# Nahid_s.net
KiCad netlist of a schematic drawn in Altium Designer
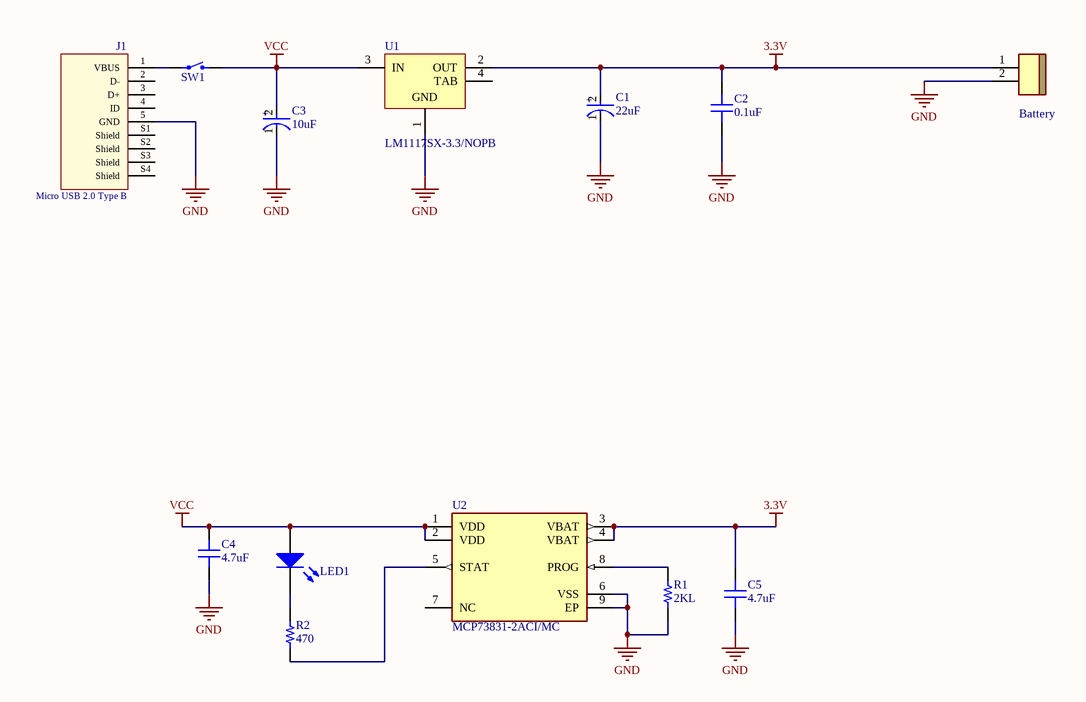
[diagram p0: Nahid's.SchDoc]

(export (version "E")
  (design (tool "Eeschema 10.0.6"))
  (components
    (comp (ref "Battery")
      (value "Battery")
      (footprint "JST B2B-PH-K")
      (description "Connector Header Through Hole 0.079\" (2.00mm)")
      (fields (field (name "PARTNUMBER") "B2B-PH-K-S(LF)(SN)"))
      (libsource (lib "Conn Terminal") (part "JST BxB-PH-K 2Pin"))
    )
    (comp (ref "C1")
      (value "22uF")
      (footprint "FP-EEH-G-MFG")
      (description "Conductive Polymer Hybrid Aluminum Electrolytic Capacitors 470uF ±20% 25V RADIAL SMT 10x10.2mm")
      (fields (field (name "TOLERANCE") "20%"))
      (libsource (lib "Altium Content Vault") (part "a00bbbee19879c290e62620ae7e47b1"))
    )
    (comp (ref "C2")
      (value "0.1uF")
      (footprint "CAP 0603_1608")
      (description "SMT Capacitor")
      (libsource (lib "Capacitor") (part "Cap 0603"))
    )
    (comp (ref "C3")
      (value "10uF")
      (footprint "FP-EEH-G-MFG")
      (description "Conductive Polymer Hybrid Aluminum Electrolytic Capacitors 470uF ±20% 25V RADIAL SMT 10x10.2mm")
      (fields (field (name "TOLERANCE") "20%"))
      (libsource (lib "Altium Content Vault") (part "a00bbbee19879c290e62620ae7e47b1"))
    )
    (comp (ref "C4")
      (value "4.7uF")
      (footprint "CAP 0603_1608")
      (description "SMT Capacitor")
      (libsource (lib "Capacitor") (part "Cap 0603"))
    )
    (comp (ref "C5")
      (value "4.7uF")
      (footprint "CAP 0603_1608")
      (description "SMT Capacitor")
      (libsource (lib "Capacitor") (part "Cap 0603"))
    )
    (comp (ref "J1")
      (value "Micro USB 2.0 Type B")
      (footprint "629105150521")
      (description "Micro USB 2.0 Type B Horizontal SMT 5 Contacts High Current WR-COM")
      (fields (field (name "PARTNUMBER") "629105150521") (field (name "PUBLISHER") "Wurth Elektronik"))
      (libsource (lib "Conn Usb") (part "Micro USB 2.0 Type B Horizontal (SMD) 629105150521"))
    )
    (comp (ref "LED1")
      (value "LED SMD 0603 BLUE")
      (footprint "LED_0603_RED")
      (libsource (lib "Led") (part "LED SMD 0603 BLUE"))
    )
    (comp (ref "R1")
      (value "2KL")
      (footprint "RES 0402_1005")
      (description "SMT Resistor")
      (libsource (lib "Resistor") (part "Res 0402"))
    )
    (comp (ref "R2")
      (value "470")
      (footprint "RES 0402_1005")
      (description "SMT Resistor")
      (libsource (lib "Resistor") (part "Res 0402"))
    )
    (comp (ref "SW1")
      (value "Tactile 2PIN 6X3.5mm H4.57mm (SMD)")
      (footprint "SWPBS_SPST_6X3X5")
      (description "Tactile Switch SPST-NO Top Actuated Surface Mount")
      (fields (field (name "PARTNUMBER") "FSMSMTR-ND"))
      (libsource (lib "Switch") (part "Tactile 2PIN 6X3.5mm H4.57mm (SMD)"))
    )
    (comp (ref "U1")
      (value "LM1117SX-3.3/NOPB")
      (footprint "KTT0003B_N")
      (description "800mA Low-Dropout Linear Regulator, 3-pin TO-263, Pb-Free")
      (fields (field (name "MANUFACTURER") "Texas Instruments"))
      (libsource (lib "Altium Content Vault") (part "PM-REG-LM1086-SOT4"))
    )
    (comp (ref "U2")
      (value "MCP73831-2ACI/MC")
      (footprint "FP-C04-123-MFG")
      (description "IC CONTROLLER LI-ION 4.2V 8DFN")
      (fields
        (field (name "OCTOPART") "https://octopart.com/mcp73831-2aci%2Fmc-microchip-16517355")
        (field (name "MANUFACTURER") "Microchip")
      )
      (libsource (lib "Altium Content Vault") (part "ff4aef3c73132f256b0e29225c28959"))
    )
  )
  (nets
    (net (code "1") (name "3.3V") (class "Default")
      (node (ref "Battery") (pin "1") (pinfunction "1_1") (pintype "passive"))
      (node (ref "C1") (pin "2") (pinfunction "A_2") (pintype "passive"))
      (node (ref "C2") (pin "2") (pinfunction "2_2") (pintype "passive"))
      (node (ref "C5") (pin "2") (pinfunction "2_2") (pintype "passive"))
      (node (ref "U1") (pin "2") (pinfunction "OUT_2") (pintype "power_in"))
      (node (ref "U2") (pin "3") (pinfunction "VBAT_3") (pintype "output"))
      (node (ref "U2") (pin "4") (pinfunction "VBAT_4") (pintype "output"))
    )
    (net (code "2") (name "GND") (class "Default")
      (node (ref "Battery") (pin "2") (pinfunction "2_2") (pintype "passive"))
      (node (ref "C1") (pin "1") (pinfunction "C_1") (pintype "passive"))
      (node (ref "C2") (pin "1") (pinfunction "1_1") (pintype "passive"))
      (node (ref "C3") (pin "1") (pinfunction "C_1") (pintype "passive"))
      (node (ref "C4") (pin "1") (pinfunction "1_1") (pintype "passive"))
      (node (ref "C5") (pin "1") (pinfunction "1_1") (pintype "passive"))
      (node (ref "J1") (pin "5") (pinfunction "GND_5") (pintype "passive"))
      (node (ref "R1") (pin "1") (pinfunction "1_1") (pintype "passive"))
      (node (ref "U1") (pin "1") (pinfunction "GND_1") (pintype "power_in"))
      (node (ref "U2") (pin "6") (pinfunction "VSS_6") (pintype "power_in"))
      (node (ref "U2") (pin "9") (pinfunction "EP_9") (pintype "power_in"))
    )
    (net (code "3") (name "Net-(J1-VBUS)") (class "Default")
      (node (ref "J1") (pin "1") (pinfunction "VBUS_1") (pintype "passive"))
      (node (ref "SW1") (pin "1") (pinfunction "1_1") (pintype "passive"))
    )
    (net (code "4") (name "Net-(LED1-K)") (class "Default")
      (node (ref "LED1") (pin "2") (pinfunction "K_2") (pintype "passive"))
      (node (ref "R2") (pin "2") (pinfunction "2_2") (pintype "passive"))
    )
    (net (code "5") (name "Net-(U2-PROG)") (class "Default")
      (node (ref "R1") (pin "2") (pinfunction "2_2") (pintype "passive"))
      (node (ref "U2") (pin "8") (pinfunction "PROG_8") (pintype "input"))
    )
    (net (code "6") (name "Net-(U2-STAT)") (class "Default")
      (node (ref "R2") (pin "1") (pinfunction "1_1") (pintype "passive"))
      (node (ref "U2") (pin "5") (pinfunction "STAT_5") (pintype "output"))
    )
    (net (code "7") (name "VCC") (class "Default")
      (node (ref "C3") (pin "2") (pinfunction "A_2") (pintype "passive"))
      (node (ref "C4") (pin "2") (pinfunction "2_2") (pintype "passive"))
      (node (ref "LED1") (pin "1") (pinfunction "A_1") (pintype "passive"))
      (node (ref "SW1") (pin "2") (pinfunction "2_2") (pintype "passive"))
      (node (ref "U1") (pin "3") (pinfunction "IN_3") (pintype "power_in"))
      (node (ref "U2") (pin "1") (pinfunction "VDD_1") (pintype "power_in"))
      (node (ref "U2") (pin "2") (pinfunction "VDD_2") (pintype "power_in"))
    )
    (net (code "8") (name "unconnected-(J1-D+-Pad3)") (class "Default")
      (node (ref "J1") (pin "3") (pinfunction "D+_3") (pintype "passive"))
    )
    (net (code "9") (name "unconnected-(J1-D--Pad2)") (class "Default")
      (node (ref "J1") (pin "2") (pinfunction "D-_2") (pintype "passive"))
    )
    (net (code "10") (name "unconnected-(J1-ID-Pad4)") (class "Default")
      (node (ref "J1") (pin "4") (pinfunction "ID_4") (pintype "passive"))
    )
    (net (code "11") (name "unconnected-(J1-Shield-PadS1)") (class "Default")
      (node (ref "J1") (pin "S1") (pinfunction "Shield_S1") (pintype "passive"))
    )
    (net (code "12") (name "unconnected-(J1-Shield-PadS2)") (class "Default")
      (node (ref "J1") (pin "S2") (pinfunction "Shield_S2") (pintype "passive"))
    )
    (net (code "13") (name "unconnected-(J1-Shield-PadS3)") (class "Default")
      (node (ref "J1") (pin "S3") (pinfunction "Shield_S3") (pintype "passive"))
    )
    (net (code "14") (name "unconnected-(J1-Shield-PadS4)") (class "Default")
      (node (ref "J1") (pin "S4") (pinfunction "Shield_S4") (pintype "passive"))
    )
    (net (code "15") (name "unconnected-(U1-TAB-Pad4)") (class "Default")
      (node (ref "U1") (pin "4") (pinfunction "TAB_4") (pintype "power_in"))
    )
    (net (code "16") (name "unconnected-(U2-NC-Pad7)") (class "Default")
      (node (ref "U2") (pin "7") (pinfunction "NC_7") (pintype "passive"))
    )
  )
)
